# wctrl_star.net
KiCad netlist of a schematic drawn in EAGLE
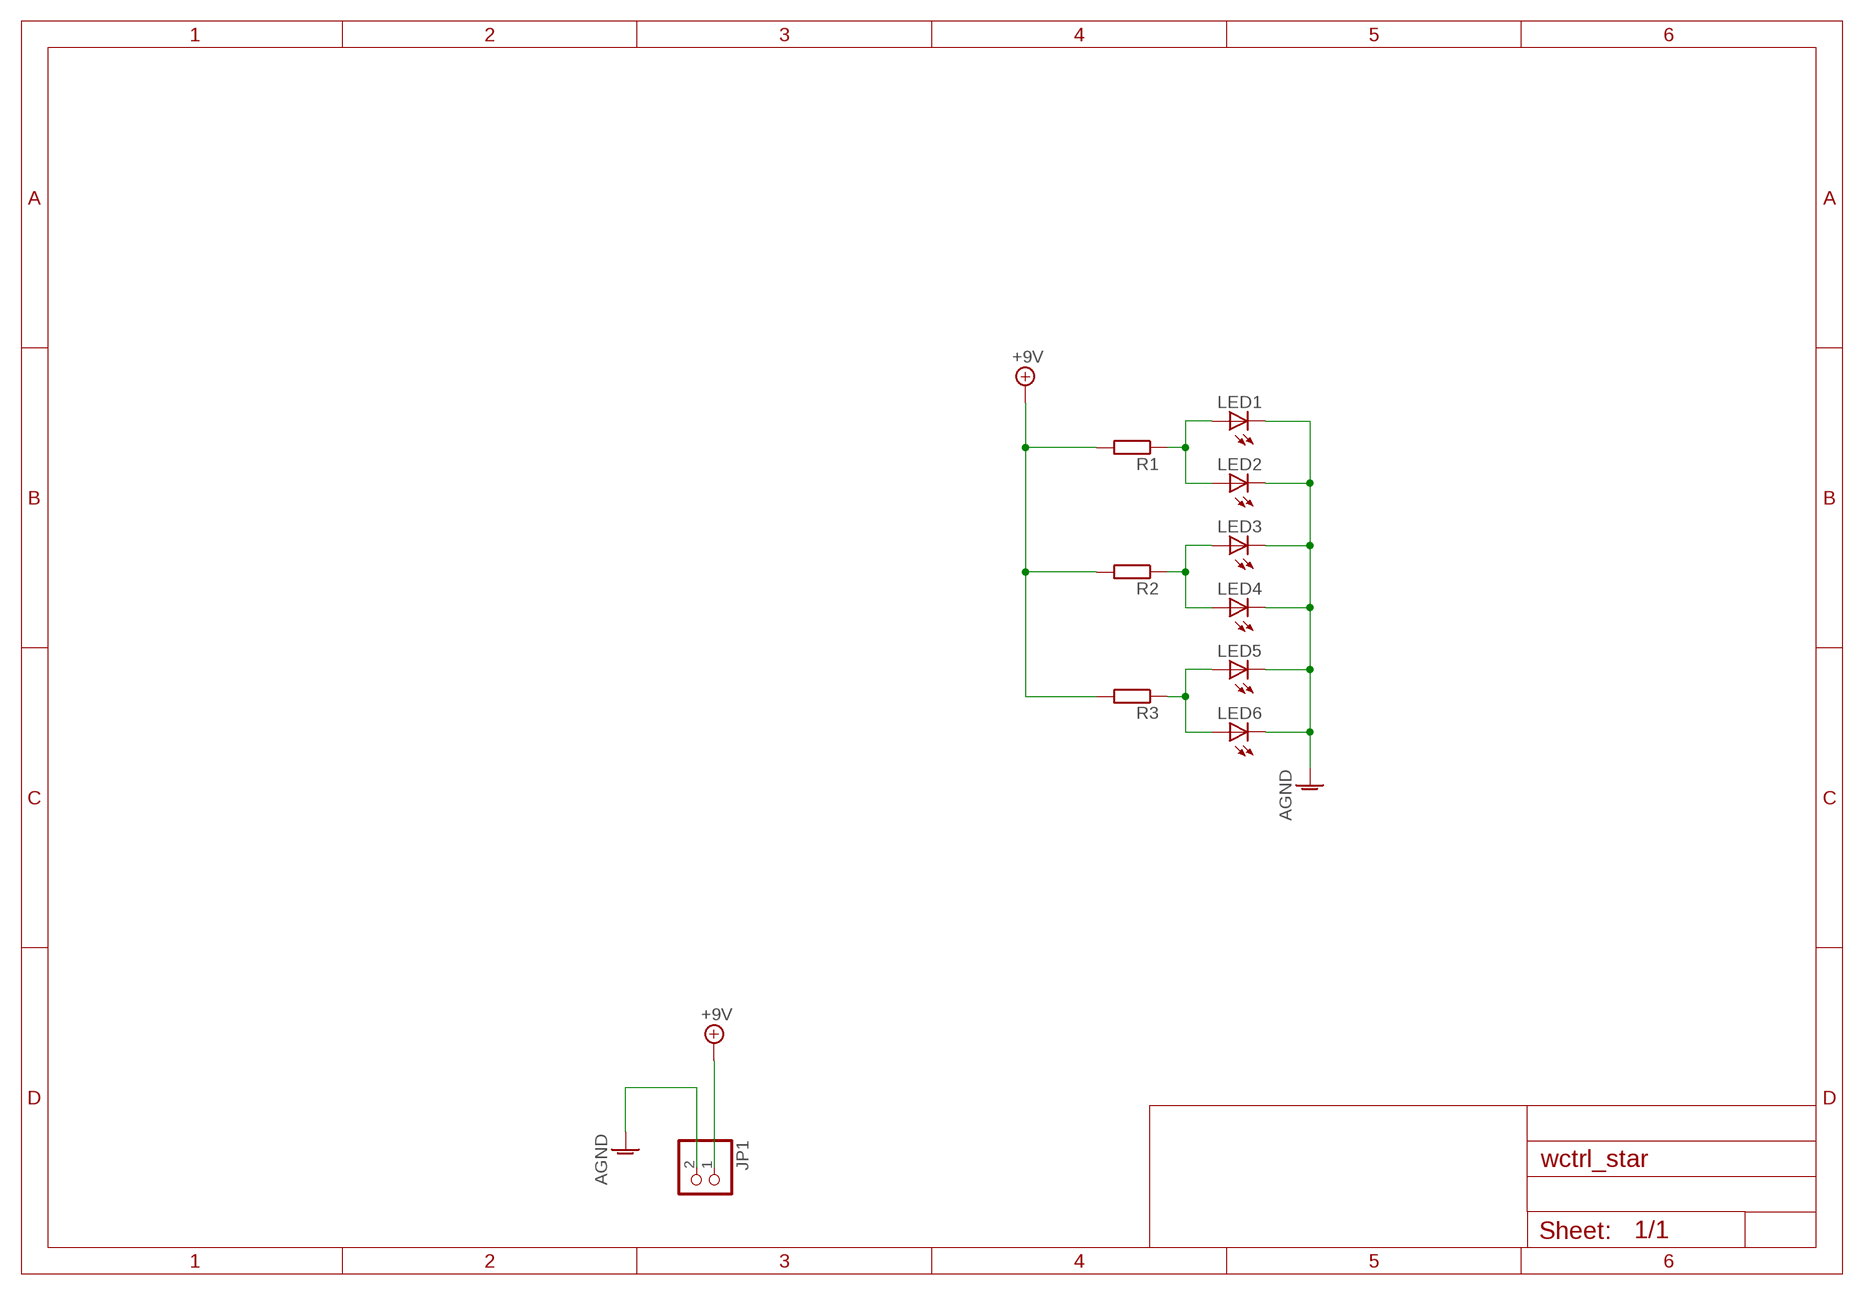
[diagram p0: schematic, sheet 1]

(export (version "E")
  (design (tool "Eeschema 10.0.6"))
  (components
    (comp (ref "JP1")
      (value "PINHD-1X2")
      (footprint "eagle-import:1X02")
      (libsource (lib "eagle-import") (part "PINHD-1X2"))
    )
    (comp (ref "LED1")
      (value "LED3MM")
      (footprint "eagle-import:LED3MM")
      (libsource (lib "eagle-import") (part "LED3MM"))
    )
    (comp (ref "LED2")
      (value "LED3MM")
      (footprint "eagle-import:LED3MM")
      (libsource (lib "eagle-import") (part "LED3MM"))
    )
    (comp (ref "LED3")
      (value "LED3MM")
      (footprint "eagle-import:LED3MM")
      (libsource (lib "eagle-import") (part "LED3MM"))
    )
    (comp (ref "LED4")
      (value "LED3MM")
      (footprint "eagle-import:LED3MM")
      (libsource (lib "eagle-import") (part "LED3MM"))
    )
    (comp (ref "LED5")
      (value "LED3MM")
      (footprint "eagle-import:LED3MM")
      (libsource (lib "eagle-import") (part "LED3MM"))
    )
    (comp (ref "LED6")
      (value "LED3MM")
      (footprint "eagle-import:LED3MM")
      (libsource (lib "eagle-import") (part "LED3MM"))
    )
    (comp (ref "R1")
      (value "R-EU_0207/10")
      (footprint "eagle-import:0207_10")
      (libsource (lib "eagle-import") (part "R-EU_0207/10"))
    )
    (comp (ref "R2")
      (value "R-EU_0207/10")
      (footprint "eagle-import:0207_10")
      (libsource (lib "eagle-import") (part "R-EU_0207/10"))
    )
    (comp (ref "R3")
      (value "R-EU_0207/10")
      (footprint "eagle-import:0207_10")
      (libsource (lib "eagle-import") (part "R-EU_0207/10"))
    )
  )
  (nets
    (net (code "1") (name "+9V") (class "Default")
      (node (ref "JP1") (pin "1") (pinfunction "1_1") (pintype "passive"))
      (node (ref "R1") (pin "2") (pinfunction "2_2") (pintype "passive"))
      (node (ref "R2") (pin "2") (pinfunction "2_2") (pintype "passive"))
      (node (ref "R3") (pin "2") (pinfunction "2_2") (pintype "passive"))
    )
    (net (code "2") (name "AGND") (class "Default")
      (node (ref "JP1") (pin "2") (pinfunction "2_2") (pintype "passive"))
      (node (ref "LED1") (pin "K") (pinfunction "C_K") (pintype "passive"))
      (node (ref "LED2") (pin "K") (pinfunction "C_K") (pintype "passive"))
      (node (ref "LED3") (pin "K") (pinfunction "C_K") (pintype "passive"))
      (node (ref "LED4") (pin "K") (pinfunction "C_K") (pintype "passive"))
      (node (ref "LED5") (pin "K") (pinfunction "C_K") (pintype "passive"))
      (node (ref "LED6") (pin "K") (pinfunction "C_K") (pintype "passive"))
    )
    (net (code "3") (name "Net-(LED1-PadA)") (class "Default")
      (node (ref "LED1") (pin "A") (pinfunction "A_A") (pintype "passive"))
      (node (ref "LED2") (pin "A") (pinfunction "A_A") (pintype "passive"))
      (node (ref "R1") (pin "1") (pinfunction "1_1") (pintype "passive"))
    )
    (net (code "4") (name "Net-(LED3-PadA)") (class "Default")
      (node (ref "LED3") (pin "A") (pinfunction "A_A") (pintype "passive"))
      (node (ref "LED4") (pin "A") (pinfunction "A_A") (pintype "passive"))
      (node (ref "R2") (pin "1") (pinfunction "1_1") (pintype "passive"))
    )
    (net (code "5") (name "Net-(LED5-PadA)") (class "Default")
      (node (ref "LED5") (pin "A") (pinfunction "A_A") (pintype "passive"))
      (node (ref "LED6") (pin "A") (pinfunction "A_A") (pintype "passive"))
      (node (ref "R3") (pin "1") (pinfunction "1_1") (pintype "passive"))
    )
  )
)
